# LaptopPower_Top_RevA.net
KiCad netlist of a schematic drawn in Altium Designer
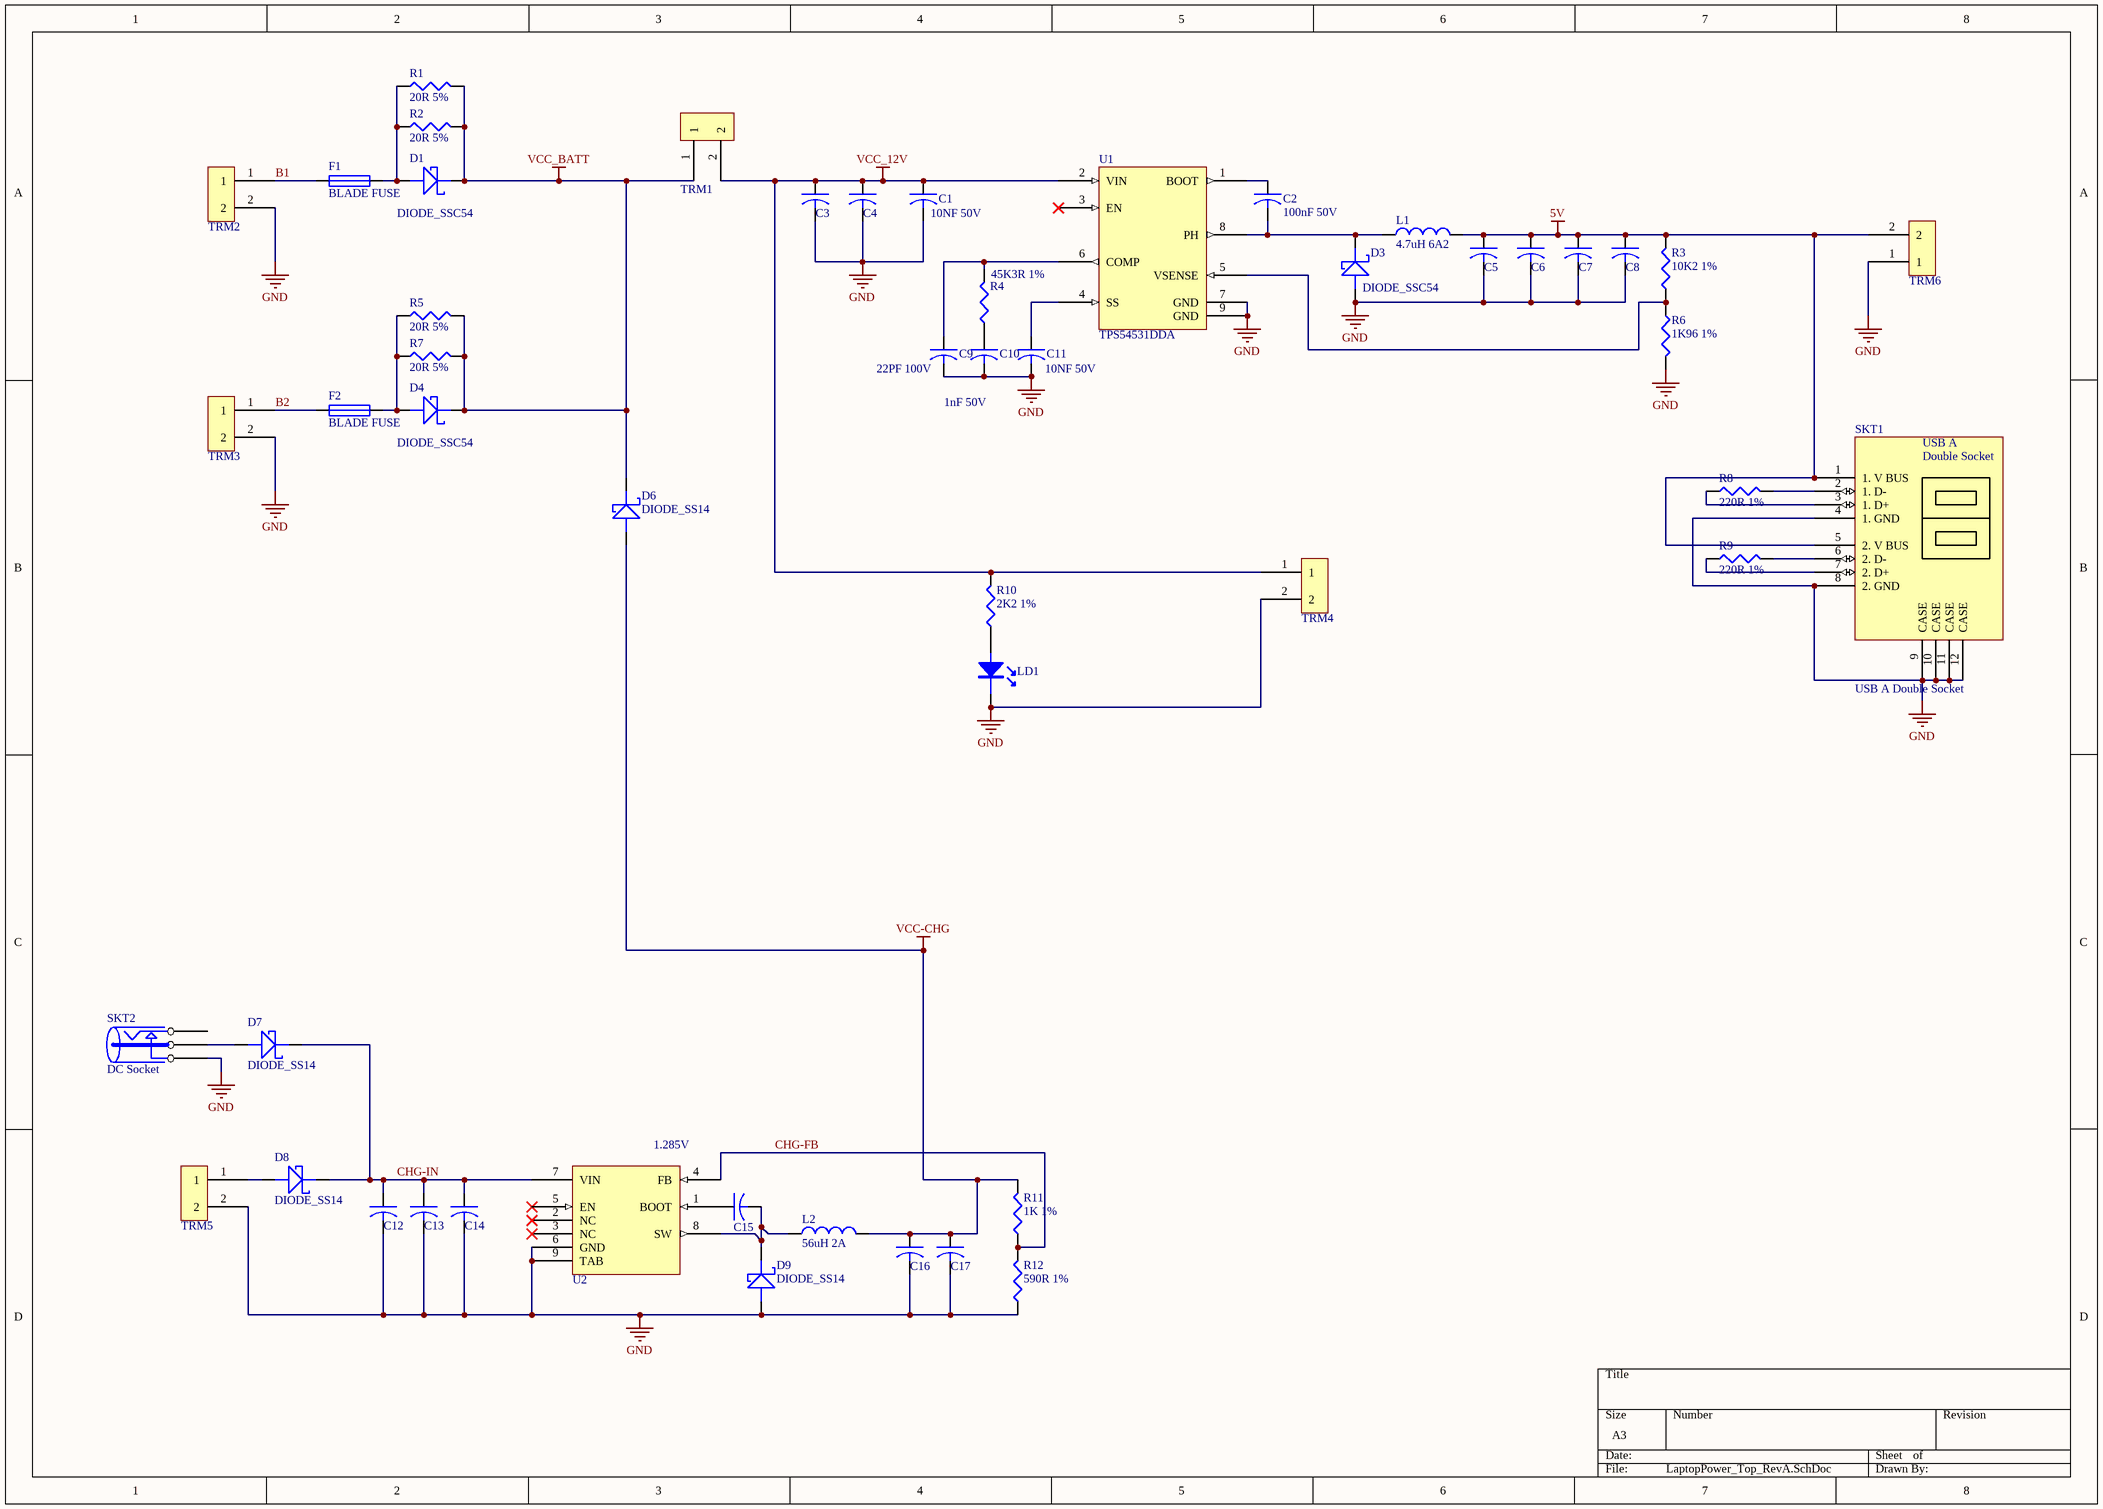
[diagram p0: LaptopPower_Top_RevA.SchDoc]

(export (version "E")
  (design (tool "Eeschema 10.0.6"))
  (components
    (comp (ref "C1")
      (value "10NF 50V")
      (footprint "0603")
      (description "CAP CER 10NF 50V 10% X7R 0603")
      (fields (field (name "MANUFACTURER") "Murata"))
      (libsource (lib "Regulators") (part "CAP_10NF_50V_10%_0603"))
    )
    (comp (ref "C2")
      (value "100nF 50V")
      (footprint "0603")
      (description "CAP CER 100nF 50V 10% X7R 0603")
      (fields (field (name "MANUFACTURER") "Murata"))
      (libsource (lib "Caps") (part "CAP_100NF_50V_10%_0603"))
    )
    (comp (ref "C3")
      (value "10UF 25V")
      (footprint "1206")
      (description "CAP CER 10UF 25V 10% X5R 1206")
      (fields (field (name "MANUFACTURER") "Murata"))
      (libsource (lib "Caps") (part "CAP_10UF_25V_10%_1206"))
    )
    (comp (ref "C4")
      (value "10UF 25V")
      (footprint "1206")
      (description "CAP CER 10UF 25V 10% X5R 1206")
      (fields (field (name "MANUFACTURER") "Murata"))
      (libsource (lib "Caps") (part "CAP_10UF_25V_10%_1206"))
    )
    (comp (ref "C5")
      (value "10UF 25V")
      (footprint "1206")
      (description "CAP CER 10UF 25V 10% X5R 1206")
      (fields (field (name "MANUFACTURER") "Murata"))
      (libsource (lib "Caps") (part "CAP_10UF_25V_10%_1206"))
    )
    (comp (ref "C6")
      (value "10UF 25V")
      (footprint "1206")
      (description "CAP CER 10UF 25V 10% X5R 1206")
      (fields (field (name "MANUFACTURER") "Murata"))
      (libsource (lib "Caps") (part "CAP_10UF_25V_10%_1206"))
    )
    (comp (ref "C7")
      (value "10UF 25V")
      (footprint "1206")
      (description "CAP CER 10UF 25V 10% X5R 1206")
      (fields (field (name "MANUFACTURER") "Murata"))
      (libsource (lib "Caps") (part "CAP_10UF_25V_10%_1206"))
    )
    (comp (ref "C8")
      (value "10UF 25V")
      (footprint "1206")
      (description "CAP CER 10UF 25V 10% X5R 1206")
      (fields (field (name "MANUFACTURER") "Murata"))
      (libsource (lib "Caps") (part "CAP_10UF_25V_10%_1206"))
    )
    (comp (ref "C9")
      (value "22PF 100V")
      (footprint "0603")
      (description "CAP CER 22PF 100V 5% NP0 0603")
      (fields (field (name "MANUFACTURER") "Murata"))
      (libsource (lib "Caps") (part "CAP_22PF_100V_5%_0603"))
    )
    (comp (ref "C10")
      (value "1nF 50V")
      (footprint "0603")
      (description "CAP CER 1nF 50V 10% X7R 0603")
      (fields (field (name "MANUFACTURER") "Murata"))
      (libsource (lib "Caps") (part "CAP_1NF_50V_10%_0603"))
    )
    (comp (ref "C11")
      (value "10NF 50V")
      (footprint "0603")
      (description "CAP CER 10NF 50V 10% X7R 0603")
      (fields (field (name "MANUFACTURER") "Murata"))
      (libsource (lib "Regulators") (part "CAP_10NF_50V_10%_0603"))
    )
    (comp (ref "C12")
      (value "10UF 25V")
      (footprint "1206")
      (description "CAP CER 10UF 25V 10% X5R 1206")
      (fields (field (name "MANUFACTURER") "Murata"))
      (libsource (lib "Caps") (part "CAP_10UF_25V_10%_1206"))
    )
    (comp (ref "C13")
      (value "10UF 25V")
      (footprint "1206")
      (description "CAP CER 10UF 25V 10% X5R 1206")
      (fields (field (name "MANUFACTURER") "Murata"))
      (libsource (lib "Caps") (part "CAP_10UF_25V_10%_1206"))
    )
    (comp (ref "C14")
      (value "100nF 50V")
      (footprint "0603")
      (description "CAP CER 100nF 50V 10% X7R 0603")
      (fields (field (name "MANUFACTURER") "Murata"))
      (libsource (lib "PowerDistributor") (part "CAP_100NF_50V_10%_0603"))
    )
    (comp (ref "C15")
      (value "10NF 50V")
      (footprint "0603")
      (description "CAP CER 10NF 50V 10% X7R 0603")
      (fields (field (name "MANUFACTURER") "Murata"))
      (libsource (lib "PowerDistributor") (part "CAP_10NF_50V_10%_0603"))
    )
    (comp (ref "C16")
      (value "10UF 25V")
      (footprint "1206")
      (description "CAP CER 10UF 25V 10% X5R 1206")
      (fields (field (name "MANUFACTURER") "Murata"))
      (libsource (lib "Caps") (part "CAP_10UF_25V_10%_1206"))
    )
    (comp (ref "C17")
      (value "10UF 25V")
      (footprint "1206")
      (description "CAP CER 10UF 25V 10% X5R 1206")
      (fields (field (name "MANUFACTURER") "Murata"))
      (libsource (lib "Caps") (part "CAP_10UF_25V_10%_1206"))
    )
    (comp (ref "D1")
      (value "DIODE_SSC54")
      (footprint "DO-214AB")
      (description "Schottky Diode, 5A, 40V SSC54, DO214AB")
      (fields (field (name "MANUFACTURER") "Vishay"))
      (libsource (lib "Regulators") (part "DIODE_SSC54"))
    )
    (comp (ref "D3")
      (value "DIODE_SSC54")
      (footprint "DO-214AB")
      (description "Schottky Diode, 5A, 40V SSC54, DO214AB")
      (fields (field (name "MANUFACTURER") "Vishay"))
      (libsource (lib "Regulators") (part "DIODE_SSC54"))
    )
    (comp (ref "D4")
      (value "DIODE_SSC54")
      (footprint "DO-214AB")
      (description "Schottky Diode, 5A, 40V SSC54, DO214AB")
      (fields (field (name "MANUFACTURER") "Vishay"))
      (libsource (lib "Regulators") (part "DIODE_SSC54"))
    )
    (comp (ref "D6")
      (value "DIODE_SS14")
      (footprint "DO-214AC")
      (description "Schottky Diode, 1A, 40V SS14")
      (fields (field (name "MANUFACTURER") "Fairchild"))
      (libsource (lib "PowerDistributor") (part "DIODE_SS14"))
    )
    (comp (ref "D7")
      (value "DIODE_SS14")
      (footprint "DO-214AC")
      (description "Schottky Diode, 1A, 40V SS14")
      (fields (field (name "MANUFACTURER") "Fairchild"))
      (libsource (lib "Semiconductors") (part "DIODE_SS14"))
    )
    (comp (ref "D8")
      (value "DIODE_SS14")
      (footprint "DO-214AC")
      (description "Schottky Diode, 1A, 40V SS14")
      (fields (field (name "MANUFACTURER") "Fairchild"))
      (libsource (lib "Semiconductors") (part "DIODE_SS14"))
    )
    (comp (ref "D9")
      (value "DIODE_SS14")
      (footprint "DO-214AC")
      (description "Schottky Diode, 1A, 40V SS14")
      (fields (field (name "MANUFACTURER") "Fairchild"))
      (libsource (lib "PowerDistributor") (part "DIODE_SS14"))
    )
    (comp (ref "F1")
      (value "BLADE FUSE")
      (footprint "FUSEHOLDER_BLADE")
      (description "FUSE CLIP BLADE 500V 30A PCB")
      (fields (field (name "MANUFACTURER") "Keystone Electronics"))
      (libsource (lib "PowerDistributor") (part "FUSE_BLADE_500V_30A_PCB"))
    )
    (comp (ref "F2")
      (value "BLADE FUSE")
      (footprint "FUSEHOLDER_BLADE")
      (description "FUSE CLIP BLADE 500V 30A PCB")
      (fields (field (name "MANUFACTURER") "Keystone Electronics"))
      (libsource (lib "PowerDistributor") (part "FUSE_BLADE_500V_30A_PCB"))
    )
    (comp (ref "L1")
      (value "4.7uH 6A2")
      (footprint "Wurth744771156")
      (description "FIXED IND 4.7UH 6.2A 34 MOHM")
      (fields (field (name "MANUFACTURER") "Wurth Electronics Inc"))
      (libsource (lib "Inductors") (part "IND_4.7uH_6A2"))
    )
    (comp (ref "L2")
      (value "56uH 2A")
      (footprint "Wurth744771156")
      (description "FIXED IND 56UH 2.01A 110 MOHM")
      (fields (field (name "MANUFACTURER") "Wurth Electronics Inc"))
      (libsource (lib "PowerDistributor") (part "IND_56uH_2.01A"))
    )
    (comp (ref "LD1")
      (value "Green LED 0805")
      (footprint "0805DIODE")
      (description "WL-SMCW SMD CHIP LED WATERCLEAR")
      (fields (field (name "MANUFACTURER") "Wurth"))
      (libsource (lib "Semiconductors") (part "LED_Green_0805"))
    )
    (comp (ref "R1")
      (value "20R 5%")
      (footprint "2512")
      (description "Resistor, 20R, 5%, 2512")
      (fields (field (name "MANUFACTURER") "Stackpole Electronics Inc"))
      (libsource (lib "Resistors") (part "RES_20R_5%_2512"))
    )
    (comp (ref "R2")
      (value "20R 5%")
      (footprint "2512")
      (description "Resistor, 20R, 5%, 2512")
      (fields (field (name "MANUFACTURER") "Stackpole Electronics Inc"))
      (libsource (lib "Resistors") (part "RES_20R_5%_2512"))
    )
    (comp (ref "R3")
      (value "10K2 1%")
      (footprint "0603")
      (description "Resistor, 10K2, 1%, 0603")
      (fields (field (name "MANUFACTURER") "Yageo"))
      (libsource (lib "Resistors") (part "RES_10K2_1%_0603"))
    )
    (comp (ref "R4")
      (value "45K3R 1%")
      (footprint "0603")
      (description "Resistor, 45K3, 1%, 0603")
      (fields (field (name "MANUFACTURER") "Bourns Inc"))
      (libsource (lib "Resistors") (part "RES_45K3_1%_0603"))
    )
    (comp (ref "R5")
      (value "20R 5%")
      (footprint "2512")
      (description "Resistor, 20R, 5%, 2512")
      (fields (field (name "MANUFACTURER") "Stackpole Electronics Inc"))
      (libsource (lib "Resistors") (part "RES_20R_5%_2512"))
    )
    (comp (ref "R6")
      (value "1K96 1%")
      (footprint "0603")
      (description "Resistor, 1K96, 1%, 0603")
      (fields (field (name "MANUFACTURER") "Yageo"))
      (libsource (lib "Resistors") (part "RES_1K96_1%_0603"))
    )
    (comp (ref "R7")
      (value "20R 5%")
      (footprint "2512")
      (description "Resistor, 20R, 5%, 2512")
      (fields (field (name "MANUFACTURER") "Stackpole Electronics Inc"))
      (libsource (lib "Resistors") (part "RES_20R_5%_2512"))
    )
    (comp (ref "R8")
      (value "220R 1%")
      (footprint "0603")
      (description "Resistor, 220R, 1%, 0603")
      (fields (field (name "MANUFACTURER") "Bourns Inc"))
      (libsource (lib "Resistors") (part "RES_220R_1%_0603"))
    )
    (comp (ref "R9")
      (value "220R 1%")
      (footprint "0603")
      (description "Resistor, 220R, 1%, 0603")
      (fields (field (name "MANUFACTURER") "Bourns Inc"))
      (libsource (lib "Resistors") (part "RES_220R_1%_0603"))
    )
    (comp (ref "R10")
      (value "2K2 1%")
      (footprint "0603")
      (description "Resistor, 2K2, 1%, 0603")
      (fields (field (name "MANUFACTURER") "Bourns Inc"))
      (libsource (lib "Resistors") (part "RES_2K2_1%_0603"))
    )
    (comp (ref "R11")
      (value "1K 1%")
      (footprint "0603")
      (description "Resistor, 1K, 1%, 0603")
      (fields (field (name "MANUFACTURER") "Bourns Inc"))
      (libsource (lib "PowerDistributor") (part "RES_1K_1%_0603"))
    )
    (comp (ref "R12")
      (value "590R 1%")
      (footprint "0603")
      (description "Resistor, 590R, 1%, 0603")
      (fields (field (name "MANUFACTURER") "Bourns Inc"))
      (libsource (lib "PowerDistributor") (part "RES_590R_1%_0603"))
    )
    (comp (ref "SKT1")
      (value "USB A Double Socket")
      (footprint "USB_A_DoubleSocket")
      (fields (field (name "PARTNO") "P1301"))
      (libsource (lib "Hardware") (part "USB_A_Double"))
    )
    (comp (ref "SKT2")
      (value "DC Socket")
      (footprint "SKT_PWR")
      (libsource (lib "Hardware") (part "SOCKET_DC"))
    )
    (comp (ref "TRM1")
      (value "Wurth 2way screw terminal")
      (footprint "TERM_2POS_HORIZ_5.08MM")
      (description "TERM BLOCK 2POS HORIZ 5.08MM T/H")
      (fields (field (name "MANUFACTURER") "Wurth Electronics Inc"))
      (libsource (lib "Hardware") (part "TRM_2way_ScrewTerminal"))
    )
    (comp (ref "TRM2")
      (value "Wurth 2way screw terminal")
      (footprint "TERM_2POS_HORIZ_5.08MM")
      (description "TERM BLOCK 2POS HORIZ 5.08MM T/H")
      (fields (field (name "MANUFACTURER") "Wurth Electronics Inc"))
      (libsource (lib "") (part "TRM_2way_ScrewTerminal_1"))
    )
    (comp (ref "TRM3")
      (value "Wurth 2way screw terminal")
      (footprint "TERM_2POS_HORIZ_5.08MM")
      (description "TERM BLOCK 2POS HORIZ 5.08MM T/H")
      (fields (field (name "MANUFACTURER") "Wurth Electronics Inc"))
      (libsource (lib "") (part "TRM_2way_ScrewTerminal_1"))
    )
    (comp (ref "TRM4")
      (value "Wurth 2way screw terminal")
      (footprint "TERM_2POS_HORIZ_5.08MM")
      (description "TERM BLOCK 2POS HORIZ 5.08MM T/H")
      (fields (field (name "MANUFACTURER") "Wurth Electronics Inc"))
      (libsource (lib "") (part "TRM_2way_ScrewTerminal_2"))
    )
    (comp (ref "TRM5")
      (value "Wurth 2way screw terminal")
      (footprint "TERM_2POS_HORIZ_5.08MM")
      (description "TERM BLOCK 2POS HORIZ 5.08MM T/H")
      (fields (field (name "MANUFACTURER") "Wurth Electronics Inc"))
      (libsource (lib "") (part "TRM_2way_ScrewTerminal_1"))
    )
    (comp (ref "TRM6")
      (value "Wurth 2way screw terminal")
      (footprint "TERM_2POS_HORIZ_5.08MM")
      (description "TERM BLOCK 2POS HORIZ 5.08MM T/H")
      (fields (field (name "MANUFACTURER") "Wurth Electronics Inc"))
      (libsource (lib "") (part "TRM_2way_ScrewTerminal_3"))
    )
    (comp (ref "U1")
      (value "TPS54531DDA")
      (footprint "PSOP-8")
      (description "SMPS")
      (fields (field (name "MANUFACTURER") "TI"))
      (libsource (lib "IC") (part "IC_SMPS_TPS54531"))
    )
    (comp (ref "U2")
      (value "Buck Reg")
      (footprint "PSOP-8")
      (description "IC REG BUCK 5V 1A 8SOPWRPAD")
      (fields (field (name "MANUFACTURER") "Texas Instruments"))
      (libsource (lib "PowerDistributor") (part "IC_REG_LM22675"))
    )
  )
  (nets
    (net (code "1") (name "/B1") (class "Default")
      (node (ref "F1") (pin "1") (pintype "passive"))
      (node (ref "TRM2") (pin "1") (pinfunction "1_1") (pintype "tri_state"))
    )
    (net (code "2") (name "/B2") (class "Default")
      (node (ref "F2") (pin "1") (pintype "passive"))
      (node (ref "TRM3") (pin "1") (pinfunction "1_1") (pintype "tri_state"))
    )
    (net (code "3") (name "/CHG-FB") (class "Default")
      (node (ref "R11") (pin "1") (pintype "passive"))
      (node (ref "R12") (pin "2") (pintype "passive"))
      (node (ref "U2") (pin "4") (pinfunction "FB_4") (pintype "input"))
    )
    (net (code "4") (name "/CHG-IN") (class "Default")
      (node (ref "C12") (pin "1") (pinfunction "1_1") (pintype "passive"))
      (node (ref "C13") (pin "1") (pinfunction "1_1") (pintype "passive"))
      (node (ref "C14") (pin "1") (pinfunction "1_1") (pintype "passive"))
      (node (ref "D7") (pin "K") (pinfunction "K_K") (pintype "passive"))
      (node (ref "D8") (pin "K") (pinfunction "K_K") (pintype "passive"))
      (node (ref "U2") (pin "7") (pinfunction "VIN_7") (pintype "power_in"))
    )
    (net (code "5") (name "5V") (class "Default")
      (node (ref "C5") (pin "1") (pinfunction "1_1") (pintype "passive"))
      (node (ref "C6") (pin "1") (pinfunction "1_1") (pintype "passive"))
      (node (ref "C7") (pin "1") (pinfunction "1_1") (pintype "passive"))
      (node (ref "C8") (pin "1") (pinfunction "1_1") (pintype "passive"))
      (node (ref "L1") (pin "2") (pinfunction "2_2") (pintype "passive"))
      (node (ref "R3") (pin "2") (pintype "passive"))
      (node (ref "SKT1") (pin "1") (pinfunction "1._V_BUS_1") (pintype "power_in"))
      (node (ref "SKT1") (pin "5") (pinfunction "2._V_BUS_5") (pintype "power_in"))
      (node (ref "TRM6") (pin "2") (pinfunction "2_2") (pintype "tri_state"))
    )
    (net (code "6") (name "GND") (class "Default")
      (node (ref "C1") (pin "2") (pinfunction "2_2") (pintype "passive"))
      (node (ref "C10") (pin "2") (pinfunction "2_2") (pintype "passive"))
      (node (ref "C11") (pin "2") (pinfunction "2_2") (pintype "passive"))
      (node (ref "C12") (pin "2") (pinfunction "2_2") (pintype "passive"))
      (node (ref "C13") (pin "2") (pinfunction "2_2") (pintype "passive"))
      (node (ref "C14") (pin "2") (pinfunction "2_2") (pintype "passive"))
      (node (ref "C16") (pin "2") (pinfunction "2_2") (pintype "passive"))
      (node (ref "C17") (pin "2") (pinfunction "2_2") (pintype "passive"))
      (node (ref "C3") (pin "2") (pinfunction "2_2") (pintype "passive"))
      (node (ref "C4") (pin "2") (pinfunction "2_2") (pintype "passive"))
      (node (ref "C5") (pin "2") (pinfunction "2_2") (pintype "passive"))
      (node (ref "C6") (pin "2") (pinfunction "2_2") (pintype "passive"))
      (node (ref "C7") (pin "2") (pinfunction "2_2") (pintype "passive"))
      (node (ref "C8") (pin "2") (pinfunction "2_2") (pintype "passive"))
      (node (ref "C9") (pin "2") (pinfunction "2_2") (pintype "passive"))
      (node (ref "D3") (pin "A") (pinfunction "A_A") (pintype "passive"))
      (node (ref "D9") (pin "A") (pinfunction "A_A") (pintype "passive"))
      (node (ref "LD1") (pin "K") (pintype "passive"))
      (node (ref "R12") (pin "1") (pintype "passive"))
      (node (ref "R6") (pin "2") (pintype "passive"))
      (node (ref "SKT1") (pin "10") (pinfunction "CASE_10") (pintype "power_in"))
      (node (ref "SKT1") (pin "11") (pinfunction "CASE_11") (pintype "power_in"))
      (node (ref "SKT1") (pin "12") (pinfunction "CASE_12") (pintype "power_in"))
      (node (ref "SKT1") (pin "4") (pinfunction "1._GND_4") (pintype "power_in"))
      (node (ref "SKT1") (pin "8") (pinfunction "2._GND_8") (pintype "power_in"))
      (node (ref "SKT1") (pin "9") (pinfunction "CASE_9") (pintype "power_in"))
      (node (ref "SKT2") (pin "SW") (pinfunction "SW_SW") (pintype "passive"))
      (node (ref "TRM2") (pin "2") (pinfunction "2_2") (pintype "tri_state"))
      (node (ref "TRM3") (pin "2") (pinfunction "2_2") (pintype "tri_state"))
      (node (ref "TRM4") (pin "2") (pinfunction "2_2") (pintype "tri_state"))
      (node (ref "TRM5") (pin "2") (pinfunction "2_2") (pintype "tri_state"))
      (node (ref "TRM6") (pin "1") (pinfunction "1_1") (pintype "tri_state"))
      (node (ref "U1") (pin "7") (pinfunction "GND_7") (pintype "power_in"))
      (node (ref "U1") (pin "9") (pinfunction "GND_9") (pintype "power_in"))
      (node (ref "U2") (pin "6") (pinfunction "GND_6") (pintype "power_in"))
      (node (ref "U2") (pin "9") (pinfunction "TAB_9") (pintype "power_in"))
    )
    (net (code "7") (name "Net-(C10-Pad1)") (class "Default")
      (node (ref "C10") (pin "1") (pinfunction "1_1") (pintype "passive"))
      (node (ref "R4") (pin "1") (pintype "passive"))
    )
    (net (code "8") (name "Net-(D1-PadA)") (class "Default")
      (node (ref "D1") (pin "A") (pinfunction "A_A") (pintype "passive"))
      (node (ref "F1") (pin "2") (pintype "passive"))
      (node (ref "R1") (pin "1") (pintype "passive"))
      (node (ref "R2") (pin "1") (pintype "passive"))
    )
    (net (code "9") (name "Net-(D4-PadA)") (class "Default")
      (node (ref "D4") (pin "A") (pinfunction "A_A") (pintype "passive"))
      (node (ref "F2") (pin "2") (pintype "passive"))
      (node (ref "R5") (pin "1") (pintype "passive"))
      (node (ref "R7") (pin "1") (pintype "passive"))
    )
    (net (code "10") (name "Net-(D7-PadA)") (class "Default")
      (node (ref "D7") (pin "A") (pinfunction "A_A") (pintype "passive"))
      (node (ref "SKT2") (pin "PIN") (pinfunction "PIN_PIN") (pintype "passive"))
    )
    (net (code "11") (name "Net-(D8-PadA)") (class "Default")
      (node (ref "D8") (pin "A") (pinfunction "A_A") (pintype "passive"))
      (node (ref "TRM5") (pin "1") (pinfunction "1_1") (pintype "tri_state"))
    )
    (net (code "12") (name "Net-(LD1-PadA)") (class "Default")
      (node (ref "LD1") (pin "A") (pintype "passive"))
      (node (ref "R10") (pin "1") (pintype "passive"))
    )
    (net (code "13") (name "Net-(SKT1-1._D+)") (class "Default")
      (node (ref "R8") (pin "1") (pintype "passive"))
      (node (ref "SKT1") (pin "3") (pinfunction "1._D+_3") (pintype "bidirectional"))
    )
    (net (code "14") (name "Net-(SKT1-1._D-)") (class "Default")
      (node (ref "R8") (pin "2") (pintype "passive"))
      (node (ref "SKT1") (pin "2") (pinfunction "1._D-_2") (pintype "bidirectional"))
    )
    (net (code "15") (name "Net-(SKT1-2._D+)") (class "Default")
      (node (ref "R9") (pin "1") (pintype "passive"))
      (node (ref "SKT1") (pin "7") (pinfunction "2._D+_7") (pintype "bidirectional"))
    )
    (net (code "16") (name "Net-(SKT1-2._D-)") (class "Default")
      (node (ref "R9") (pin "2") (pintype "passive"))
      (node (ref "SKT1") (pin "6") (pinfunction "2._D-_6") (pintype "bidirectional"))
    )
    (net (code "17") (name "Net-(U1-BOOT)") (class "Default")
      (node (ref "C2") (pin "1") (pinfunction "1_1") (pintype "passive"))
      (node (ref "U1") (pin "1") (pinfunction "BOOT_1") (pintype "output"))
    )
    (net (code "18") (name "Net-(U1-COMP)") (class "Default")
      (node (ref "C9") (pin "1") (pinfunction "1_1") (pintype "passive"))
      (node (ref "R4") (pin "2") (pintype "passive"))
      (node (ref "U1") (pin "6") (pinfunction "COMP_6") (pintype "output"))
    )
    (net (code "19") (name "Net-(U1-PH)") (class "Default")
      (node (ref "C2") (pin "2") (pinfunction "2_2") (pintype "passive"))
      (node (ref "D3") (pin "K") (pinfunction "K_K") (pintype "passive"))
      (node (ref "L1") (pin "1") (pinfunction "1_1") (pintype "passive"))
      (node (ref "U1") (pin "8") (pinfunction "PH_8") (pintype "output"))
    )
    (net (code "20") (name "Net-(U1-SS)") (class "Default")
      (node (ref "C11") (pin "1") (pinfunction "1_1") (pintype "passive"))
      (node (ref "U1") (pin "4") (pinfunction "SS_4") (pintype "input"))
    )
    (net (code "21") (name "Net-(U1-VSENSE)") (class "Default")
      (node (ref "R3") (pin "1") (pintype "passive"))
      (node (ref "R6") (pin "1") (pintype "passive"))
      (node (ref "U1") (pin "5") (pinfunction "VSENSE_5") (pintype "input"))
    )
    (net (code "22") (name "Net-(U2-BOOT)") (class "Default")
      (node (ref "C15") (pin "1") (pinfunction "1_1") (pintype "passive"))
      (node (ref "U2") (pin "1") (pinfunction "BOOT_1") (pintype "input"))
    )
    (net (code "23") (name "Net-(U2-SW)") (class "Default")
      (node (ref "C15") (pin "2") (pinfunction "2_2") (pintype "passive"))
      (node (ref "D9") (pin "K") (pinfunction "K_K") (pintype "passive"))
      (node (ref "L2") (pin "1") (pinfunction "1_1") (pintype "passive"))
      (node (ref "U2") (pin "8") (pinfunction "SW_8") (pintype "output"))
    )
    (net (code "24") (name "VCC-CHG") (class "Default")
      (node (ref "C16") (pin "1") (pinfunction "1_1") (pintype "passive"))
      (node (ref "C17") (pin "1") (pinfunction "1_1") (pintype "passive"))
      (node (ref "D6") (pin "A") (pinfunction "A_A") (pintype "passive"))
      (node (ref "L2") (pin "2") (pinfunction "2_2") (pintype "passive"))
      (node (ref "R11") (pin "2") (pintype "passive"))
    )
    (net (code "25") (name "VCC_12V") (class "Default")
      (node (ref "C1") (pin "1") (pinfunction "1_1") (pintype "passive"))
      (node (ref "C3") (pin "1") (pinfunction "1_1") (pintype "passive"))
      (node (ref "C4") (pin "1") (pinfunction "1_1") (pintype "passive"))
      (node (ref "R10") (pin "2") (pintype "passive"))
      (node (ref "TRM1") (pin "2") (pinfunction "2_2") (pintype "tri_state"))
      (node (ref "TRM4") (pin "1") (pinfunction "1_1") (pintype "tri_state"))
      (node (ref "U1") (pin "2") (pinfunction "VIN_2") (pintype "input"))
    )
    (net (code "26") (name "VCC_BATT") (class "Default")
      (node (ref "D1") (pin "K") (pinfunction "K_K") (pintype "passive"))
      (node (ref "D4") (pin "K") (pinfunction "K_K") (pintype "passive"))
      (node (ref "D6") (pin "K") (pinfunction "K_K") (pintype "passive"))
      (node (ref "R1") (pin "2") (pintype "passive"))
      (node (ref "R2") (pin "2") (pintype "passive"))
      (node (ref "R5") (pin "2") (pintype "passive"))
      (node (ref "R7") (pin "2") (pintype "passive"))
      (node (ref "TRM1") (pin "1") (pinfunction "1_1") (pintype "tri_state"))
    )
    (net (code "27") (name "unconnected-(SKT2-PadCOM)") (class "Default")
      (node (ref "SKT2") (pin "COM") (pinfunction "COM_COM") (pintype "passive"))
    )
    (net (code "28") (name "unconnected-(U1-EN-Pad3)") (class "Default")
      (node (ref "U1") (pin "3") (pinfunction "EN_3") (pintype "input+no_connect"))
    )
    (net (code "29") (name "unconnected-(U2-EN-Pad5)") (class "Default")
      (node (ref "U2") (pin "5") (pinfunction "EN_5") (pintype "input+no_connect"))
    )
    (net (code "30") (name "unconnected-(U2-NC-Pad2)") (class "Default")
      (node (ref "U2") (pin "2") (pinfunction "NC_2") (pintype "tri_state+no_connect"))
    )
    (net (code "31") (name "unconnected-(U2-NC-Pad3)") (class "Default")
      (node (ref "U2") (pin "3") (pinfunction "NC_3") (pintype "tri_state+no_connect"))
    )
  )
)
